# maze_expander_1_0.net
KiCad netlist of a schematic drawn in EAGLE
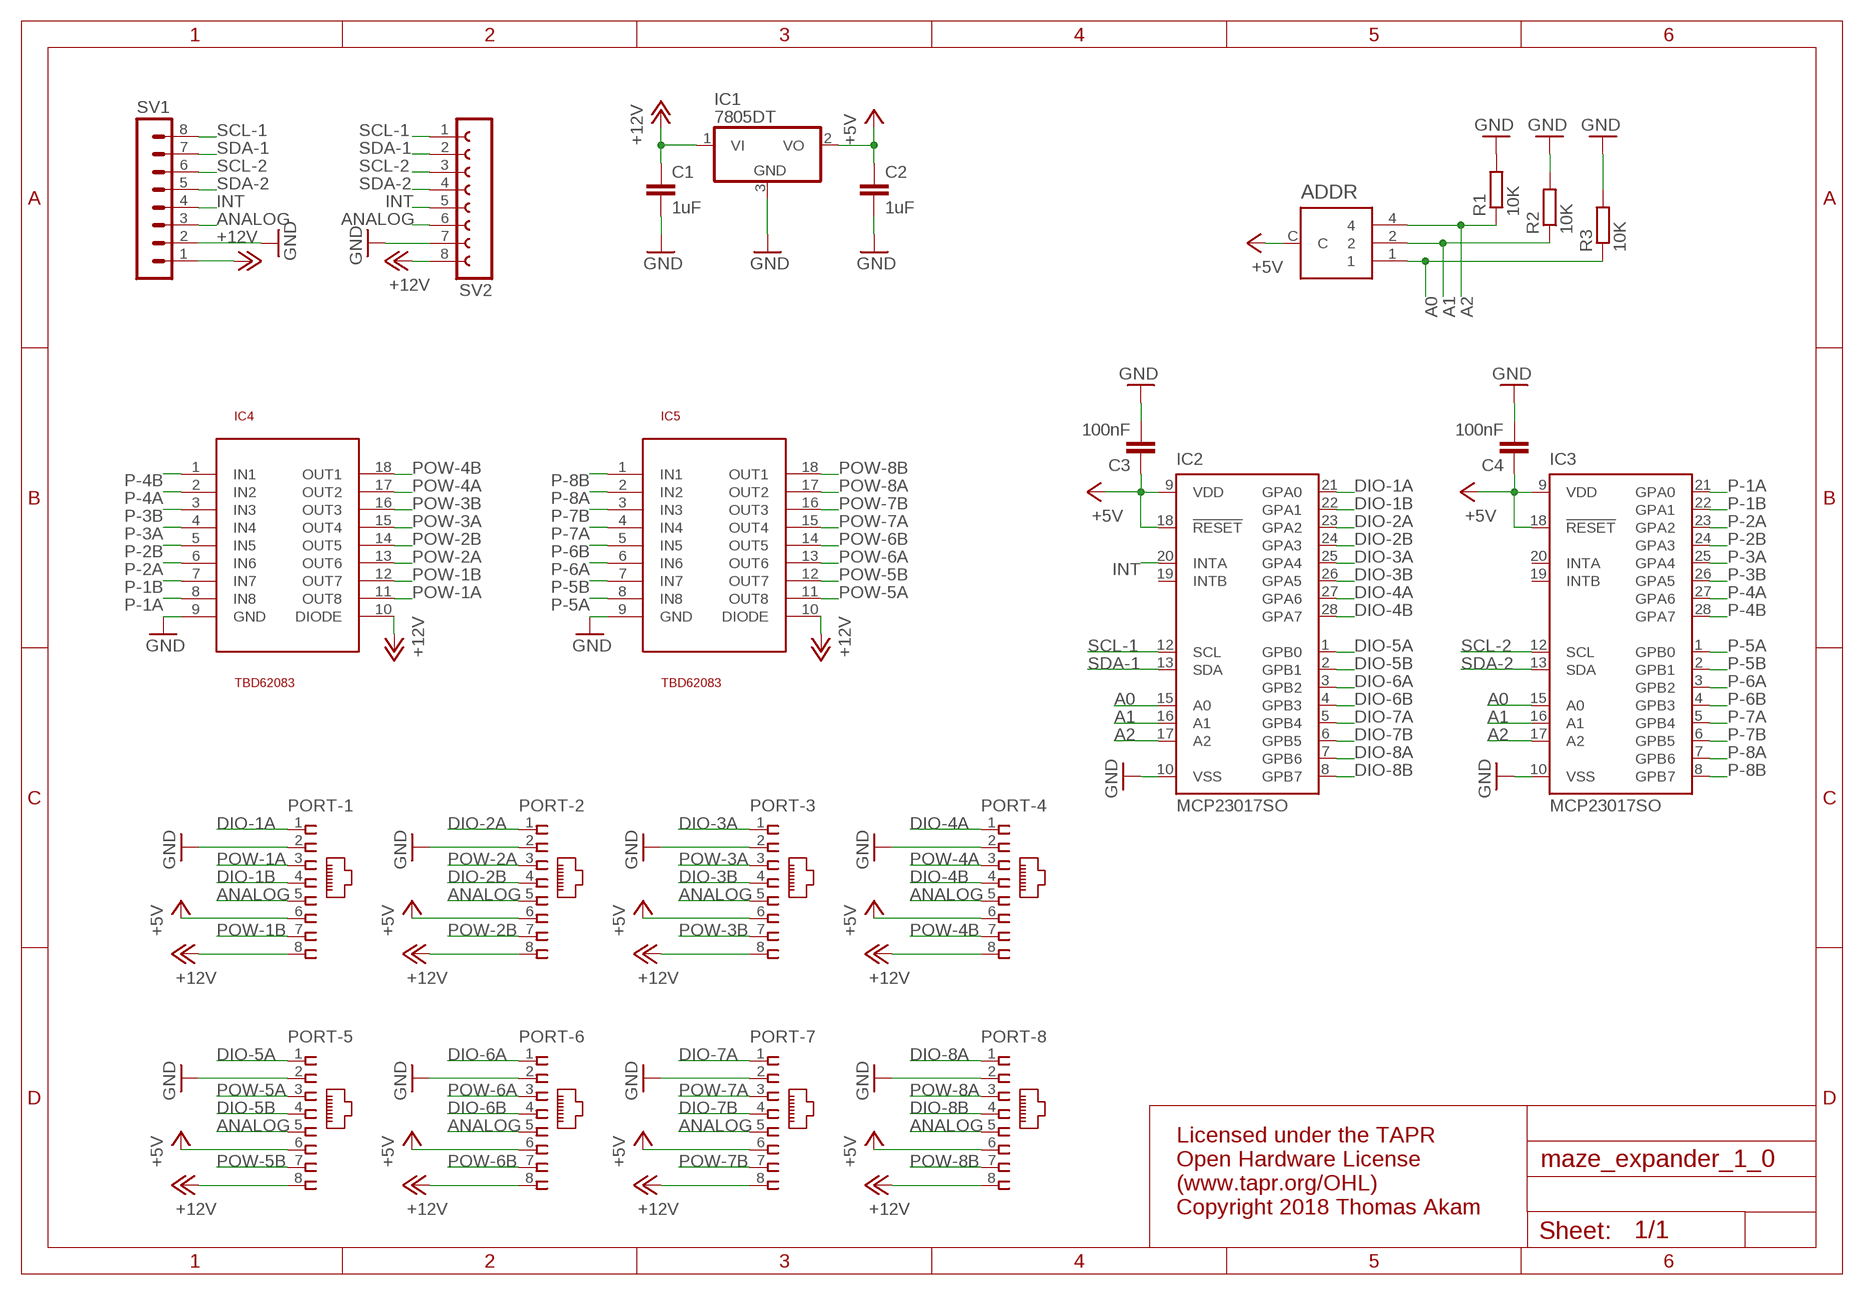
[diagram p0: schematic, sheet 1]

(export (version "E")
  (design (tool "Eeschema 10.0.6"))
  (components
    (comp (ref "ADDR")
      (value "S-8010")
      (footprint "eagle-import:S-8010")
      (libsource (lib "eagle-import") (part "S-8010"))
    )
    (comp (ref "C1")
      (value "1uF")
      (footprint "eagle-import:C0805")
      (libsource (lib "eagle-import") (part "C-EUC0805"))
    )
    (comp (ref "C2")
      (value "1uF")
      (footprint "eagle-import:C0805")
      (libsource (lib "eagle-import") (part "C-EUC0805"))
    )
    (comp (ref "C3")
      (value "100nF")
      (footprint "eagle-import:C0805")
      (libsource (lib "eagle-import") (part "C-EUC0805"))
    )
    (comp (ref "C4")
      (value "100nF")
      (footprint "eagle-import:C0805")
      (libsource (lib "eagle-import") (part "C-EUC0805"))
    )
    (comp (ref "IC1")
      (value "7805DT")
      (footprint "eagle-import:TO252")
      (libsource (lib "eagle-import") (part "78DT05"))
    )
    (comp (ref "IC2")
      (value "MCP23017SO")
      (footprint "eagle-import:SO28W")
      (fields (field (name "MF") "MICROCHIP") (field (name "MPN") "MCP23017-E/SO"))
      (libsource (lib "eagle-import") (part "MCP23017SO"))
    )
    (comp (ref "IC3")
      (value "MCP23017SO")
      (footprint "eagle-import:SO28W")
      (fields (field (name "MF") "MICROCHIP") (field (name "MPN") "MCP23017-E/SO"))
      (libsource (lib "eagle-import") (part "MCP23017SO"))
    )
    (comp (ref "IC4")
      (value "TBD62083")
      (footprint "eagle-import:SO18L")
      (libsource (lib "eagle-import") (part "ULN2803"))
    )
    (comp (ref "IC5")
      (value "TBD62083")
      (footprint "eagle-import:SO18L")
      (libsource (lib "eagle-import") (part "ULN2803"))
    )
    (comp (ref "PORT-1")
      (value "RJ45VERTICAL")
      (footprint "eagle-import:RJ45-NO-SHIELD-VERTICAL")
      (libsource (lib "eagle-import") (part "RJ45VERTICAL"))
    )
    (comp (ref "PORT-2")
      (value "RJ45VERTICAL")
      (footprint "eagle-import:RJ45-NO-SHIELD-VERTICAL")
      (libsource (lib "eagle-import") (part "RJ45VERTICAL"))
    )
    (comp (ref "PORT-3")
      (value "RJ45VERTICAL")
      (footprint "eagle-import:RJ45-NO-SHIELD-VERTICAL")
      (libsource (lib "eagle-import") (part "RJ45VERTICAL"))
    )
    (comp (ref "PORT-4")
      (value "RJ45VERTICAL")
      (footprint "eagle-import:RJ45-NO-SHIELD-VERTICAL")
      (libsource (lib "eagle-import") (part "RJ45VERTICAL"))
    )
    (comp (ref "PORT-5")
      (value "RJ45VERTICAL")
      (footprint "eagle-import:RJ45-NO-SHIELD-VERTICAL")
      (libsource (lib "eagle-import") (part "RJ45VERTICAL"))
    )
    (comp (ref "PORT-6")
      (value "RJ45VERTICAL")
      (footprint "eagle-import:RJ45-NO-SHIELD-VERTICAL")
      (libsource (lib "eagle-import") (part "RJ45VERTICAL"))
    )
    (comp (ref "PORT-7")
      (value "RJ45VERTICAL")
      (footprint "eagle-import:RJ45-NO-SHIELD-VERTICAL")
      (libsource (lib "eagle-import") (part "RJ45VERTICAL"))
    )
    (comp (ref "PORT-8")
      (value "RJ45VERTICAL")
      (footprint "eagle-import:RJ45-NO-SHIELD-VERTICAL")
      (libsource (lib "eagle-import") (part "RJ45VERTICAL"))
    )
    (comp (ref "R1")
      (value "10K")
      (footprint "eagle-import:R0805")
      (libsource (lib "eagle-import") (part "R-EU_R0805"))
    )
    (comp (ref "R2")
      (value "10K")
      (footprint "eagle-import:R0805")
      (libsource (lib "eagle-import") (part "R-EU_R0805"))
    )
    (comp (ref "R3")
      (value "10K")
      (footprint "eagle-import:R0805")
      (libsource (lib "eagle-import") (part "R-EU_R0805"))
    )
    (comp (ref "SV1")
      (value "MA08-1W")
      (footprint "eagle-import:MA08-1W")
      (libsource (lib "eagle-import") (part "MA08-1W"))
    )
    (comp (ref "SV2")
      (value "FE08W")
      (footprint "eagle-import:FE08W")
      (libsource (lib "eagle-import") (part "FE08W"))
    )
  )
  (nets
    (net (code "1") (name "+5V") (class "Default")
      (node (ref "ADDR") (pin "C") (pinfunction "C_C") (pintype "bidirectional"))
      (node (ref "C2") (pin "1") (pinfunction "1_1") (pintype "passive"))
      (node (ref "C3") (pin "1") (pinfunction "1_1") (pintype "passive"))
      (node (ref "C4") (pin "1") (pinfunction "1_1") (pintype "passive"))
      (node (ref "IC1") (pin "2") (pinfunction "VO_2") (pintype "passive"))
      (node (ref "IC2") (pin "18") (pinfunction "~{RESET}_18") (pintype "input"))
      (node (ref "IC2") (pin "9") (pinfunction "VDD_9") (pintype "power_in"))
      (node (ref "IC3") (pin "18") (pinfunction "~{RESET}_18") (pintype "input"))
      (node (ref "IC3") (pin "9") (pinfunction "VDD_9") (pintype "power_in"))
      (node (ref "PORT-1") (pin "6") (pinfunction "6_6") (pintype "passive"))
      (node (ref "PORT-2") (pin "6") (pinfunction "6_6") (pintype "passive"))
      (node (ref "PORT-3") (pin "6") (pinfunction "6_6") (pintype "passive"))
      (node (ref "PORT-4") (pin "6") (pinfunction "6_6") (pintype "passive"))
      (node (ref "PORT-5") (pin "6") (pinfunction "6_6") (pintype "passive"))
      (node (ref "PORT-6") (pin "6") (pinfunction "6_6") (pintype "passive"))
      (node (ref "PORT-7") (pin "6") (pinfunction "6_6") (pintype "passive"))
      (node (ref "PORT-8") (pin "6") (pinfunction "6_6") (pintype "passive"))
    )
    (net (code "2") (name "+12V") (class "Default")
      (node (ref "C1") (pin "1") (pinfunction "1_1") (pintype "passive"))
      (node (ref "IC1") (pin "1") (pinfunction "VI_1") (pintype "input"))
      (node (ref "IC4") (pin "10") (pinfunction "DIODE_10") (pintype "power_in"))
      (node (ref "IC5") (pin "10") (pinfunction "DIODE_10") (pintype "power_in"))
      (node (ref "PORT-1") (pin "8") (pinfunction "8_8") (pintype "passive"))
      (node (ref "PORT-2") (pin "8") (pinfunction "8_8") (pintype "passive"))
      (node (ref "PORT-3") (pin "8") (pinfunction "8_8") (pintype "passive"))
      (node (ref "PORT-4") (pin "8") (pinfunction "8_8") (pintype "passive"))
      (node (ref "PORT-5") (pin "8") (pinfunction "8_8") (pintype "passive"))
      (node (ref "PORT-6") (pin "8") (pinfunction "8_8") (pintype "passive"))
      (node (ref "PORT-7") (pin "8") (pinfunction "8_8") (pintype "passive"))
      (node (ref "PORT-8") (pin "8") (pinfunction "8_8") (pintype "passive"))
      (node (ref "SV1") (pin "1") (pinfunction "1_1") (pintype "passive"))
      (node (ref "SV2") (pin "8") (pinfunction "8_8") (pintype "passive"))
    )
    (net (code "3") (name "/A0") (class "Default")
      (node (ref "ADDR") (pin "1") (pinfunction "1_1") (pintype "bidirectional"))
      (node (ref "IC2") (pin "15") (pinfunction "A0_15") (pintype "input"))
      (node (ref "IC3") (pin "15") (pinfunction "A0_15") (pintype "input"))
      (node (ref "R3") (pin "1") (pinfunction "1_1") (pintype "passive"))
    )
    (net (code "4") (name "/A1") (class "Default")
      (node (ref "ADDR") (pin "2") (pinfunction "2_2") (pintype "bidirectional"))
      (node (ref "IC2") (pin "16") (pinfunction "A1_16") (pintype "input"))
      (node (ref "IC3") (pin "16") (pinfunction "A1_16") (pintype "input"))
      (node (ref "R2") (pin "1") (pinfunction "1_1") (pintype "passive"))
    )
    (net (code "5") (name "/A2") (class "Default")
      (node (ref "ADDR") (pin "4") (pinfunction "4_4") (pintype "bidirectional"))
      (node (ref "IC2") (pin "17") (pinfunction "A2_17") (pintype "input"))
      (node (ref "IC3") (pin "17") (pinfunction "A2_17") (pintype "input"))
      (node (ref "R1") (pin "1") (pinfunction "1_1") (pintype "passive"))
    )
    (net (code "6") (name "/ANALOG") (class "Default")
      (node (ref "PORT-1") (pin "5") (pinfunction "5_5") (pintype "passive"))
      (node (ref "PORT-2") (pin "5") (pinfunction "5_5") (pintype "passive"))
      (node (ref "PORT-3") (pin "5") (pinfunction "5_5") (pintype "passive"))
      (node (ref "PORT-4") (pin "5") (pinfunction "5_5") (pintype "passive"))
      (node (ref "PORT-5") (pin "5") (pinfunction "5_5") (pintype "passive"))
      (node (ref "PORT-6") (pin "5") (pinfunction "5_5") (pintype "passive"))
      (node (ref "PORT-7") (pin "5") (pinfunction "5_5") (pintype "passive"))
      (node (ref "PORT-8") (pin "5") (pinfunction "5_5") (pintype "passive"))
      (node (ref "SV1") (pin "3") (pinfunction "3_3") (pintype "passive"))
      (node (ref "SV2") (pin "6") (pinfunction "6_6") (pintype "passive"))
    )
    (net (code "7") (name "/DIO-1A") (class "Default")
      (node (ref "IC2") (pin "21") (pinfunction "GPA0_21") (pintype "bidirectional"))
      (node (ref "PORT-1") (pin "1") (pinfunction "1_1") (pintype "passive"))
    )
    (net (code "8") (name "/DIO-1B") (class "Default")
      (node (ref "IC2") (pin "22") (pinfunction "GPA1_22") (pintype "bidirectional"))
      (node (ref "PORT-1") (pin "4") (pinfunction "4_4") (pintype "passive"))
    )
    (net (code "9") (name "/DIO-2A") (class "Default")
      (node (ref "IC2") (pin "23") (pinfunction "GPA2_23") (pintype "bidirectional"))
      (node (ref "PORT-2") (pin "1") (pinfunction "1_1") (pintype "passive"))
    )
    (net (code "10") (name "/DIO-2B") (class "Default")
      (node (ref "IC2") (pin "24") (pinfunction "GPA3_24") (pintype "bidirectional"))
      (node (ref "PORT-2") (pin "4") (pinfunction "4_4") (pintype "passive"))
    )
    (net (code "11") (name "/DIO-3A") (class "Default")
      (node (ref "IC2") (pin "25") (pinfunction "GPA4_25") (pintype "bidirectional"))
      (node (ref "PORT-3") (pin "1") (pinfunction "1_1") (pintype "passive"))
    )
    (net (code "12") (name "/DIO-3B") (class "Default")
      (node (ref "IC2") (pin "26") (pinfunction "GPA5_26") (pintype "bidirectional"))
      (node (ref "PORT-3") (pin "4") (pinfunction "4_4") (pintype "passive"))
    )
    (net (code "13") (name "/DIO-4A") (class "Default")
      (node (ref "IC2") (pin "27") (pinfunction "GPA6_27") (pintype "bidirectional"))
      (node (ref "PORT-4") (pin "1") (pinfunction "1_1") (pintype "passive"))
    )
    (net (code "14") (name "/DIO-4B") (class "Default")
      (node (ref "IC2") (pin "28") (pinfunction "GPA7_28") (pintype "bidirectional"))
      (node (ref "PORT-4") (pin "4") (pinfunction "4_4") (pintype "passive"))
    )
    (net (code "15") (name "/DIO-5A") (class "Default")
      (node (ref "IC2") (pin "1") (pinfunction "GPB0_1") (pintype "bidirectional"))
      (node (ref "PORT-5") (pin "1") (pinfunction "1_1") (pintype "passive"))
    )
    (net (code "16") (name "/DIO-5B") (class "Default")
      (node (ref "IC2") (pin "2") (pinfunction "GPB1_2") (pintype "bidirectional"))
      (node (ref "PORT-5") (pin "4") (pinfunction "4_4") (pintype "passive"))
    )
    (net (code "17") (name "/DIO-6A") (class "Default")
      (node (ref "IC2") (pin "3") (pinfunction "GPB2_3") (pintype "bidirectional"))
      (node (ref "PORT-6") (pin "1") (pinfunction "1_1") (pintype "passive"))
    )
    (net (code "18") (name "/DIO-6B") (class "Default")
      (node (ref "IC2") (pin "4") (pinfunction "GPB3_4") (pintype "bidirectional"))
      (node (ref "PORT-6") (pin "4") (pinfunction "4_4") (pintype "passive"))
    )
    (net (code "19") (name "/DIO-7A") (class "Default")
      (node (ref "IC2") (pin "5") (pinfunction "GPB4_5") (pintype "bidirectional"))
      (node (ref "PORT-7") (pin "1") (pinfunction "1_1") (pintype "passive"))
    )
    (net (code "20") (name "/DIO-7B") (class "Default")
      (node (ref "IC2") (pin "6") (pinfunction "GPB5_6") (pintype "bidirectional"))
      (node (ref "PORT-7") (pin "4") (pinfunction "4_4") (pintype "passive"))
    )
    (net (code "21") (name "/DIO-8A") (class "Default")
      (node (ref "IC2") (pin "7") (pinfunction "GPB6_7") (pintype "bidirectional"))
      (node (ref "PORT-8") (pin "1") (pinfunction "1_1") (pintype "passive"))
    )
    (net (code "22") (name "/DIO-8B") (class "Default")
      (node (ref "IC2") (pin "8") (pinfunction "GPB7_8") (pintype "bidirectional"))
      (node (ref "PORT-8") (pin "4") (pinfunction "4_4") (pintype "passive"))
    )
    (net (code "23") (name "/INT") (class "Default")
      (node (ref "IC2") (pin "20") (pinfunction "INTA_20") (pintype "output"))
      (node (ref "SV1") (pin "4") (pinfunction "4_4") (pintype "passive"))
      (node (ref "SV2") (pin "5") (pinfunction "5_5") (pintype "passive"))
    )
    (net (code "24") (name "/P-1A") (class "Default")
      (node (ref "IC3") (pin "21") (pinfunction "GPA0_21") (pintype "bidirectional"))
      (node (ref "IC4") (pin "8") (pinfunction "IN8_8") (pintype "input"))
    )
    (net (code "25") (name "/P-1B") (class "Default")
      (node (ref "IC3") (pin "22") (pinfunction "GPA1_22") (pintype "bidirectional"))
      (node (ref "IC4") (pin "7") (pinfunction "IN7_7") (pintype "input"))
    )
    (net (code "26") (name "/P-2A") (class "Default")
      (node (ref "IC3") (pin "23") (pinfunction "GPA2_23") (pintype "bidirectional"))
      (node (ref "IC4") (pin "6") (pinfunction "IN6_6") (pintype "input"))
    )
    (net (code "27") (name "/P-2B") (class "Default")
      (node (ref "IC3") (pin "24") (pinfunction "GPA3_24") (pintype "bidirectional"))
      (node (ref "IC4") (pin "5") (pinfunction "IN5_5") (pintype "input"))
    )
    (net (code "28") (name "/P-3A") (class "Default")
      (node (ref "IC3") (pin "25") (pinfunction "GPA4_25") (pintype "bidirectional"))
      (node (ref "IC4") (pin "4") (pinfunction "IN4_4") (pintype "input"))
    )
    (net (code "29") (name "/P-3B") (class "Default")
      (node (ref "IC3") (pin "26") (pinfunction "GPA5_26") (pintype "bidirectional"))
      (node (ref "IC4") (pin "3") (pinfunction "IN3_3") (pintype "input"))
    )
    (net (code "30") (name "/P-4A") (class "Default")
      (node (ref "IC3") (pin "27") (pinfunction "GPA6_27") (pintype "bidirectional"))
      (node (ref "IC4") (pin "2") (pinfunction "IN2_2") (pintype "input"))
    )
    (net (code "31") (name "/P-4B") (class "Default")
      (node (ref "IC3") (pin "28") (pinfunction "GPA7_28") (pintype "bidirectional"))
      (node (ref "IC4") (pin "1") (pinfunction "IN1_1") (pintype "input"))
    )
    (net (code "32") (name "/P-5A") (class "Default")
      (node (ref "IC3") (pin "1") (pinfunction "GPB0_1") (pintype "bidirectional"))
      (node (ref "IC5") (pin "8") (pinfunction "IN8_8") (pintype "input"))
    )
    (net (code "33") (name "/P-5B") (class "Default")
      (node (ref "IC3") (pin "2") (pinfunction "GPB1_2") (pintype "bidirectional"))
      (node (ref "IC5") (pin "7") (pinfunction "IN7_7") (pintype "input"))
    )
    (net (code "34") (name "/P-6A") (class "Default")
      (node (ref "IC3") (pin "3") (pinfunction "GPB2_3") (pintype "bidirectional"))
      (node (ref "IC5") (pin "6") (pinfunction "IN6_6") (pintype "input"))
    )
    (net (code "35") (name "/P-6B") (class "Default")
      (node (ref "IC3") (pin "4") (pinfunction "GPB3_4") (pintype "bidirectional"))
      (node (ref "IC5") (pin "5") (pinfunction "IN5_5") (pintype "input"))
    )
    (net (code "36") (name "/P-7A") (class "Default")
      (node (ref "IC3") (pin "5") (pinfunction "GPB4_5") (pintype "bidirectional"))
      (node (ref "IC5") (pin "4") (pinfunction "IN4_4") (pintype "input"))
    )
    (net (code "37") (name "/P-7B") (class "Default")
      (node (ref "IC3") (pin "6") (pinfunction "GPB5_6") (pintype "bidirectional"))
      (node (ref "IC5") (pin "3") (pinfunction "IN3_3") (pintype "input"))
    )
    (net (code "38") (name "/P-8A") (class "Default")
      (node (ref "IC3") (pin "7") (pinfunction "GPB6_7") (pintype "bidirectional"))
      (node (ref "IC5") (pin "2") (pinfunction "IN2_2") (pintype "input"))
    )
    (net (code "39") (name "/P-8B") (class "Default")
      (node (ref "IC3") (pin "8") (pinfunction "GPB7_8") (pintype "bidirectional"))
      (node (ref "IC5") (pin "1") (pinfunction "IN1_1") (pintype "input"))
    )
    (net (code "40") (name "/POW-1A") (class "Default")
      (node (ref "IC4") (pin "11") (pinfunction "OUT8_11") (pintype "open_collector"))
      (node (ref "PORT-1") (pin "3") (pinfunction "3_3") (pintype "passive"))
    )
    (net (code "41") (name "/POW-1B") (class "Default")
      (node (ref "IC4") (pin "12") (pinfunction "OUT7_12") (pintype "open_collector"))
      (node (ref "PORT-1") (pin "7") (pinfunction "7_7") (pintype "passive"))
    )
    (net (code "42") (name "/POW-2A") (class "Default")
      (node (ref "IC4") (pin "13") (pinfunction "OUT6_13") (pintype "open_collector"))
      (node (ref "PORT-2") (pin "3") (pinfunction "3_3") (pintype "passive"))
    )
    (net (code "43") (name "/POW-2B") (class "Default")
      (node (ref "IC4") (pin "14") (pinfunction "OUT5_14") (pintype "open_collector"))
      (node (ref "PORT-2") (pin "7") (pinfunction "7_7") (pintype "passive"))
    )
    (net (code "44") (name "/POW-3A") (class "Default")
      (node (ref "IC4") (pin "15") (pinfunction "OUT4_15") (pintype "open_collector"))
      (node (ref "PORT-3") (pin "3") (pinfunction "3_3") (pintype "passive"))
    )
    (net (code "45") (name "/POW-3B") (class "Default")
      (node (ref "IC4") (pin "16") (pinfunction "OUT3_16") (pintype "open_collector"))
      (node (ref "PORT-3") (pin "7") (pinfunction "7_7") (pintype "passive"))
    )
    (net (code "46") (name "/POW-4A") (class "Default")
      (node (ref "IC4") (pin "17") (pinfunction "OUT2_17") (pintype "open_collector"))
      (node (ref "PORT-4") (pin "3") (pinfunction "3_3") (pintype "passive"))
    )
    (net (code "47") (name "/POW-4B") (class "Default")
      (node (ref "IC4") (pin "18") (pinfunction "OUT1_18") (pintype "open_collector"))
      (node (ref "PORT-4") (pin "7") (pinfunction "7_7") (pintype "passive"))
    )
    (net (code "48") (name "/POW-5A") (class "Default")
      (node (ref "IC5") (pin "11") (pinfunction "OUT8_11") (pintype "open_collector"))
      (node (ref "PORT-5") (pin "3") (pinfunction "3_3") (pintype "passive"))
    )
    (net (code "49") (name "/POW-5B") (class "Default")
      (node (ref "IC5") (pin "12") (pinfunction "OUT7_12") (pintype "open_collector"))
      (node (ref "PORT-5") (pin "7") (pinfunction "7_7") (pintype "passive"))
    )
    (net (code "50") (name "/POW-6A") (class "Default")
      (node (ref "IC5") (pin "13") (pinfunction "OUT6_13") (pintype "open_collector"))
      (node (ref "PORT-6") (pin "3") (pinfunction "3_3") (pintype "passive"))
    )
    (net (code "51") (name "/POW-6B") (class "Default")
      (node (ref "IC5") (pin "14") (pinfunction "OUT5_14") (pintype "open_collector"))
      (node (ref "PORT-6") (pin "7") (pinfunction "7_7") (pintype "passive"))
    )
    (net (code "52") (name "/POW-7A") (class "Default")
      (node (ref "IC5") (pin "15") (pinfunction "OUT4_15") (pintype "open_collector"))
      (node (ref "PORT-7") (pin "3") (pinfunction "3_3") (pintype "passive"))
    )
    (net (code "53") (name "/POW-7B") (class "Default")
      (node (ref "IC5") (pin "16") (pinfunction "OUT3_16") (pintype "open_collector"))
      (node (ref "PORT-7") (pin "7") (pinfunction "7_7") (pintype "passive"))
    )
    (net (code "54") (name "/POW-8A") (class "Default")
      (node (ref "IC5") (pin "17") (pinfunction "OUT2_17") (pintype "open_collector"))
      (node (ref "PORT-8") (pin "3") (pinfunction "3_3") (pintype "passive"))
    )
    (net (code "55") (name "/POW-8B") (class "Default")
      (node (ref "IC5") (pin "18") (pinfunction "OUT1_18") (pintype "open_collector"))
      (node (ref "PORT-8") (pin "7") (pinfunction "7_7") (pintype "passive"))
    )
    (net (code "56") (name "/SCL-1") (class "Default")
      (node (ref "IC2") (pin "12") (pinfunction "SCL_12") (pintype "input"))
      (node (ref "SV1") (pin "8") (pinfunction "8_8") (pintype "passive"))
      (node (ref "SV2") (pin "1") (pinfunction "1_1") (pintype "passive"))
    )
    (net (code "57") (name "/SCL-2") (class "Default")
      (node (ref "IC3") (pin "12") (pinfunction "SCL_12") (pintype "input"))
      (node (ref "SV1") (pin "6") (pinfunction "6_6") (pintype "passive"))
      (node (ref "SV2") (pin "3") (pinfunction "3_3") (pintype "passive"))
    )
    (net (code "58") (name "/SDA-1") (class "Default")
      (node (ref "IC2") (pin "13") (pinfunction "SDA_13") (pintype "bidirectional"))
      (node (ref "SV1") (pin "7") (pinfunction "7_7") (pintype "passive"))
      (node (ref "SV2") (pin "2") (pinfunction "2_2") (pintype "passive"))
    )
    (net (code "59") (name "/SDA-2") (class "Default")
      (node (ref "IC3") (pin "13") (pinfunction "SDA_13") (pintype "bidirectional"))
      (node (ref "SV1") (pin "5") (pinfunction "5_5") (pintype "passive"))
      (node (ref "SV2") (pin "4") (pinfunction "4_4") (pintype "passive"))
    )
    (net (code "60") (name "GND") (class "Default")
      (node (ref "C1") (pin "2") (pinfunction "2_2") (pintype "passive"))
      (node (ref "C2") (pin "2") (pinfunction "2_2") (pintype "passive"))
      (node (ref "C3") (pin "2") (pinfunction "2_2") (pintype "passive"))
      (node (ref "C4") (pin "2") (pinfunction "2_2") (pintype "passive"))
      (node (ref "IC1") (pin "3") (pinfunction "GND_3") (pintype "passive"))
      (node (ref "IC2") (pin "10") (pinfunction "VSS_10") (pintype "power_in"))
      (node (ref "IC3") (pin "10") (pinfunction "VSS_10") (pintype "power_in"))
      (node (ref "IC4") (pin "9") (pinfunction "GND_9") (pintype "power_in"))
      (node (ref "IC5") (pin "9") (pinfunction "GND_9") (pintype "power_in"))
      (node (ref "PORT-1") (pin "2") (pinfunction "2_2") (pintype "passive"))
      (node (ref "PORT-2") (pin "2") (pinfunction "2_2") (pintype "passive"))
      (node (ref "PORT-3") (pin "2") (pinfunction "2_2") (pintype "passive"))
      (node (ref "PORT-4") (pin "2") (pinfunction "2_2") (pintype "passive"))
      (node (ref "PORT-5") (pin "2") (pinfunction "2_2") (pintype "passive"))
      (node (ref "PORT-6") (pin "2") (pinfunction "2_2") (pintype "passive"))
      (node (ref "PORT-7") (pin "2") (pinfunction "2_2") (pintype "passive"))
      (node (ref "PORT-8") (pin "2") (pinfunction "2_2") (pintype "passive"))
      (node (ref "R1") (pin "2") (pinfunction "2_2") (pintype "passive"))
      (node (ref "R2") (pin "2") (pinfunction "2_2") (pintype "passive"))
      (node (ref "R3") (pin "2") (pinfunction "2_2") (pintype "passive"))
      (node (ref "SV1") (pin "2") (pinfunction "2_2") (pintype "passive"))
      (node (ref "SV2") (pin "7") (pinfunction "7_7") (pintype "passive"))
    )
    (net (code "61") (name "unconnected-(IC2-INTB-Pad19)") (class "Default")
      (node (ref "IC2") (pin "19") (pinfunction "INTB_19") (pintype "output"))
    )
    (net (code "62") (name "unconnected-(IC3-INTA-Pad20)") (class "Default")
      (node (ref "IC3") (pin "20") (pinfunction "INTA_20") (pintype "output"))
    )
    (net (code "63") (name "unconnected-(IC3-INTB-Pad19)") (class "Default")
      (node (ref "IC3") (pin "19") (pinfunction "INTB_19") (pintype "output"))
    )
  )
)
